# sanguish_2.net
KiCad netlist of a schematic drawn in EAGLE
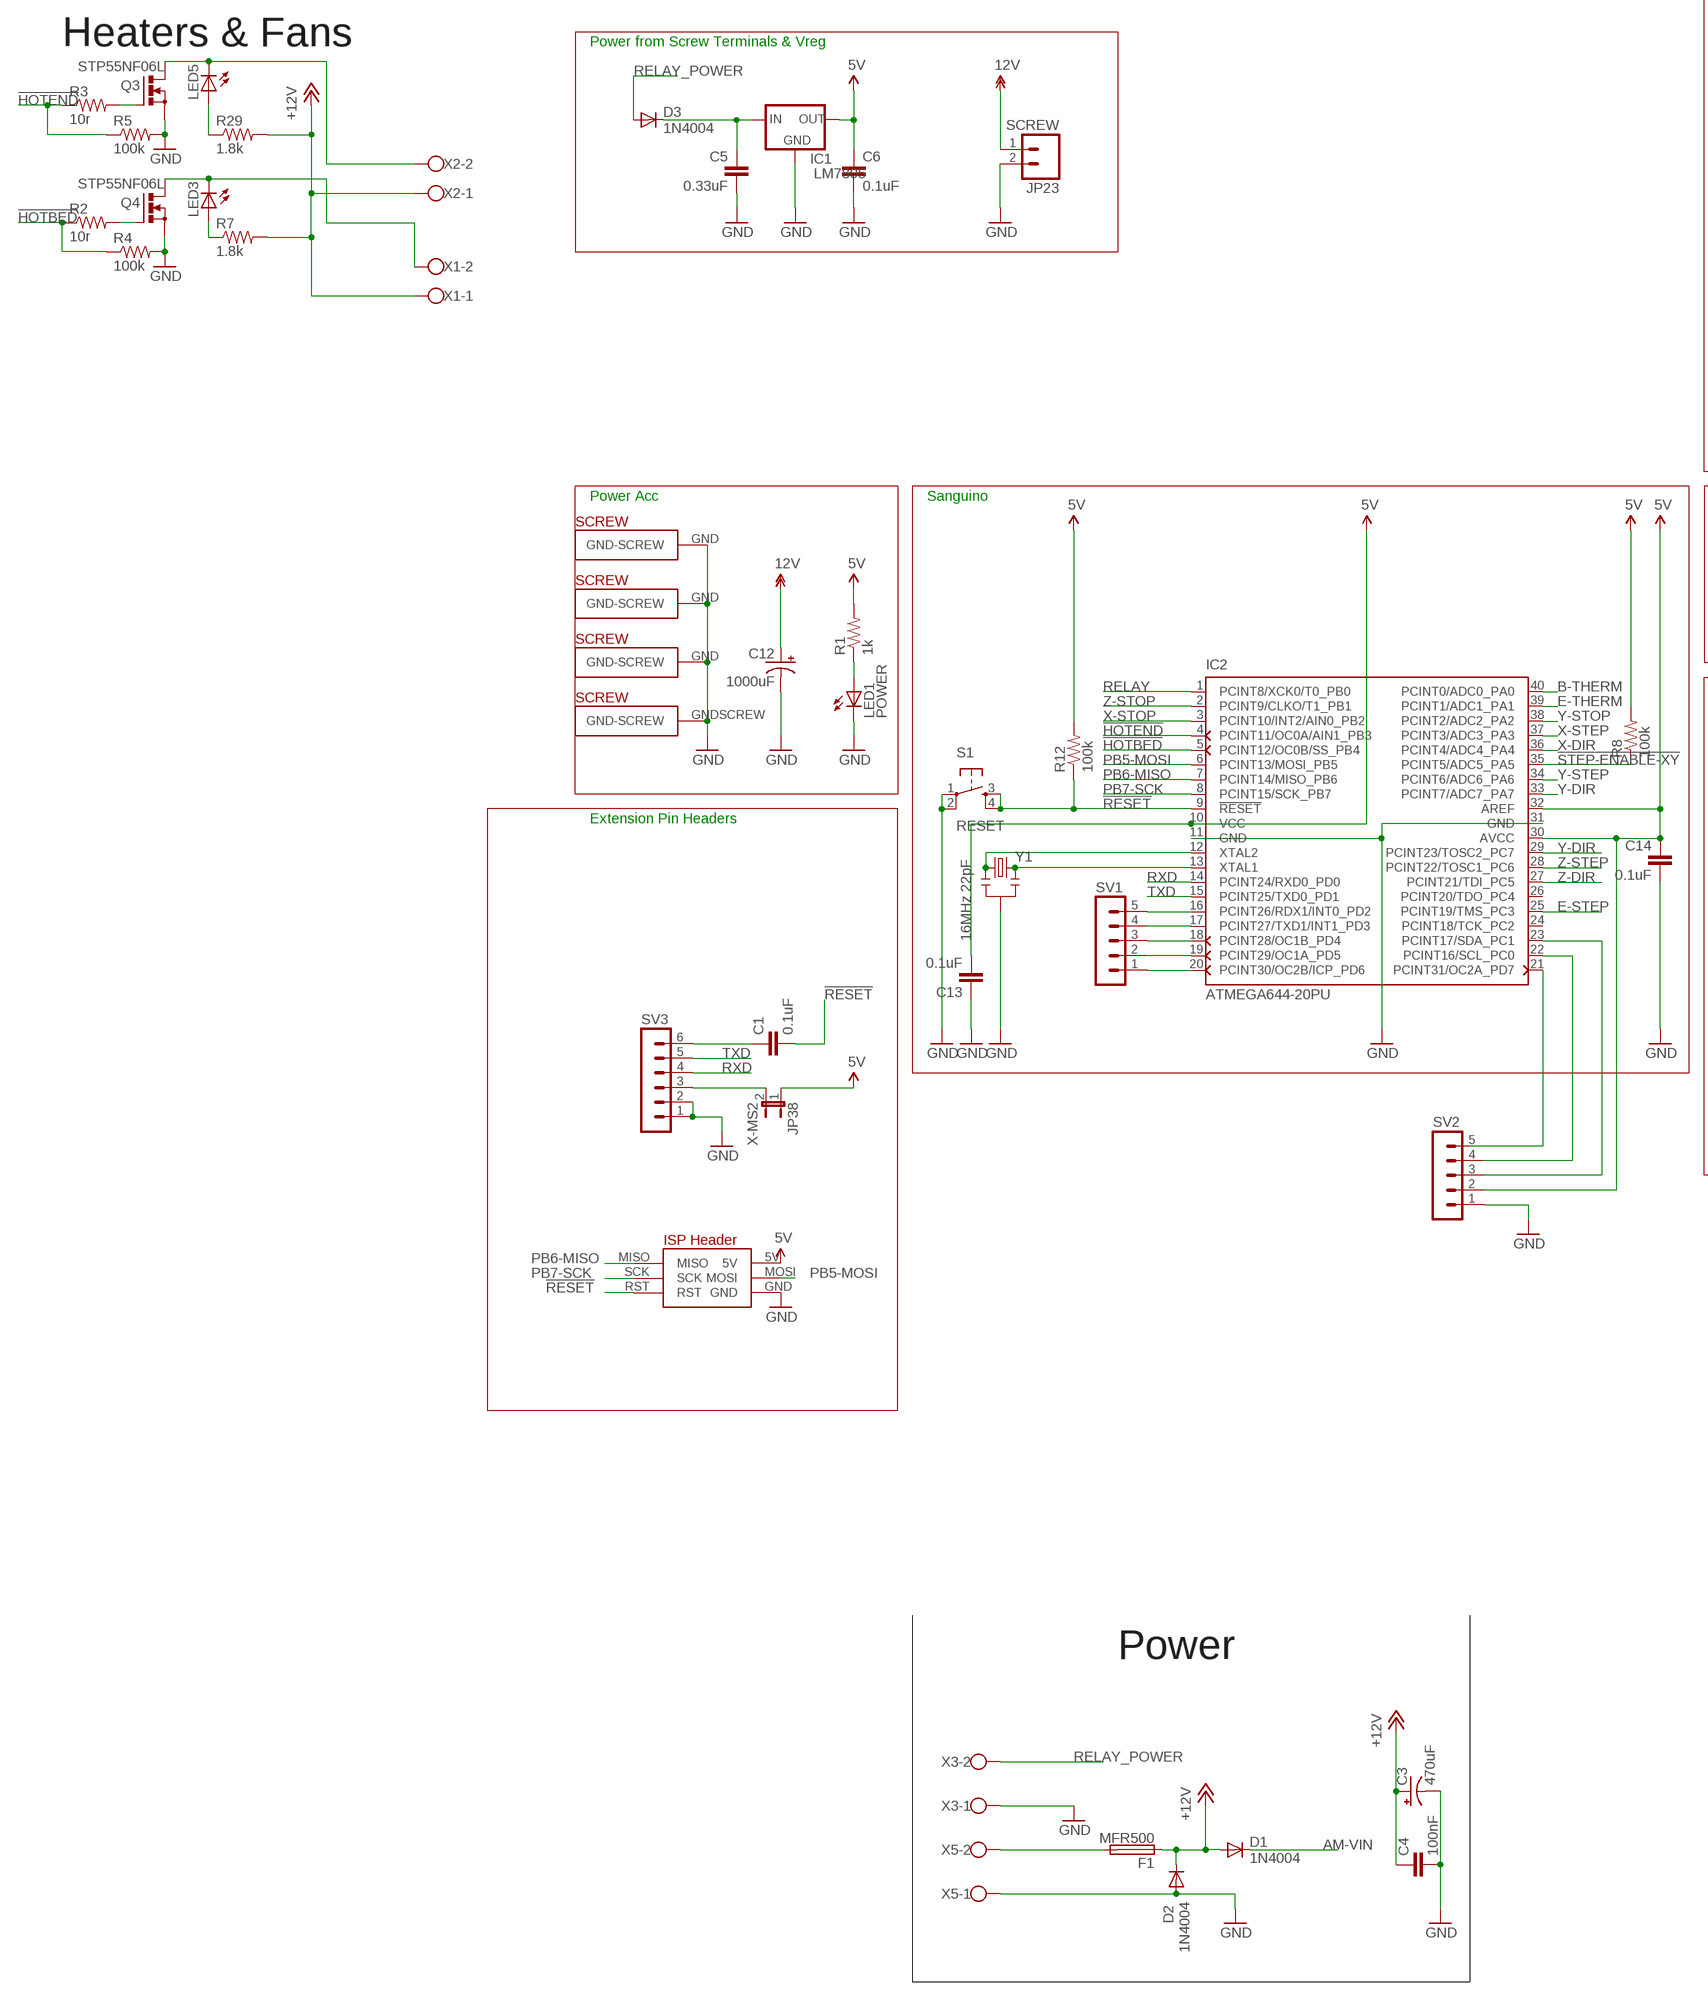
[diagram p0: schematic, sheet 1, part 1 of 2]
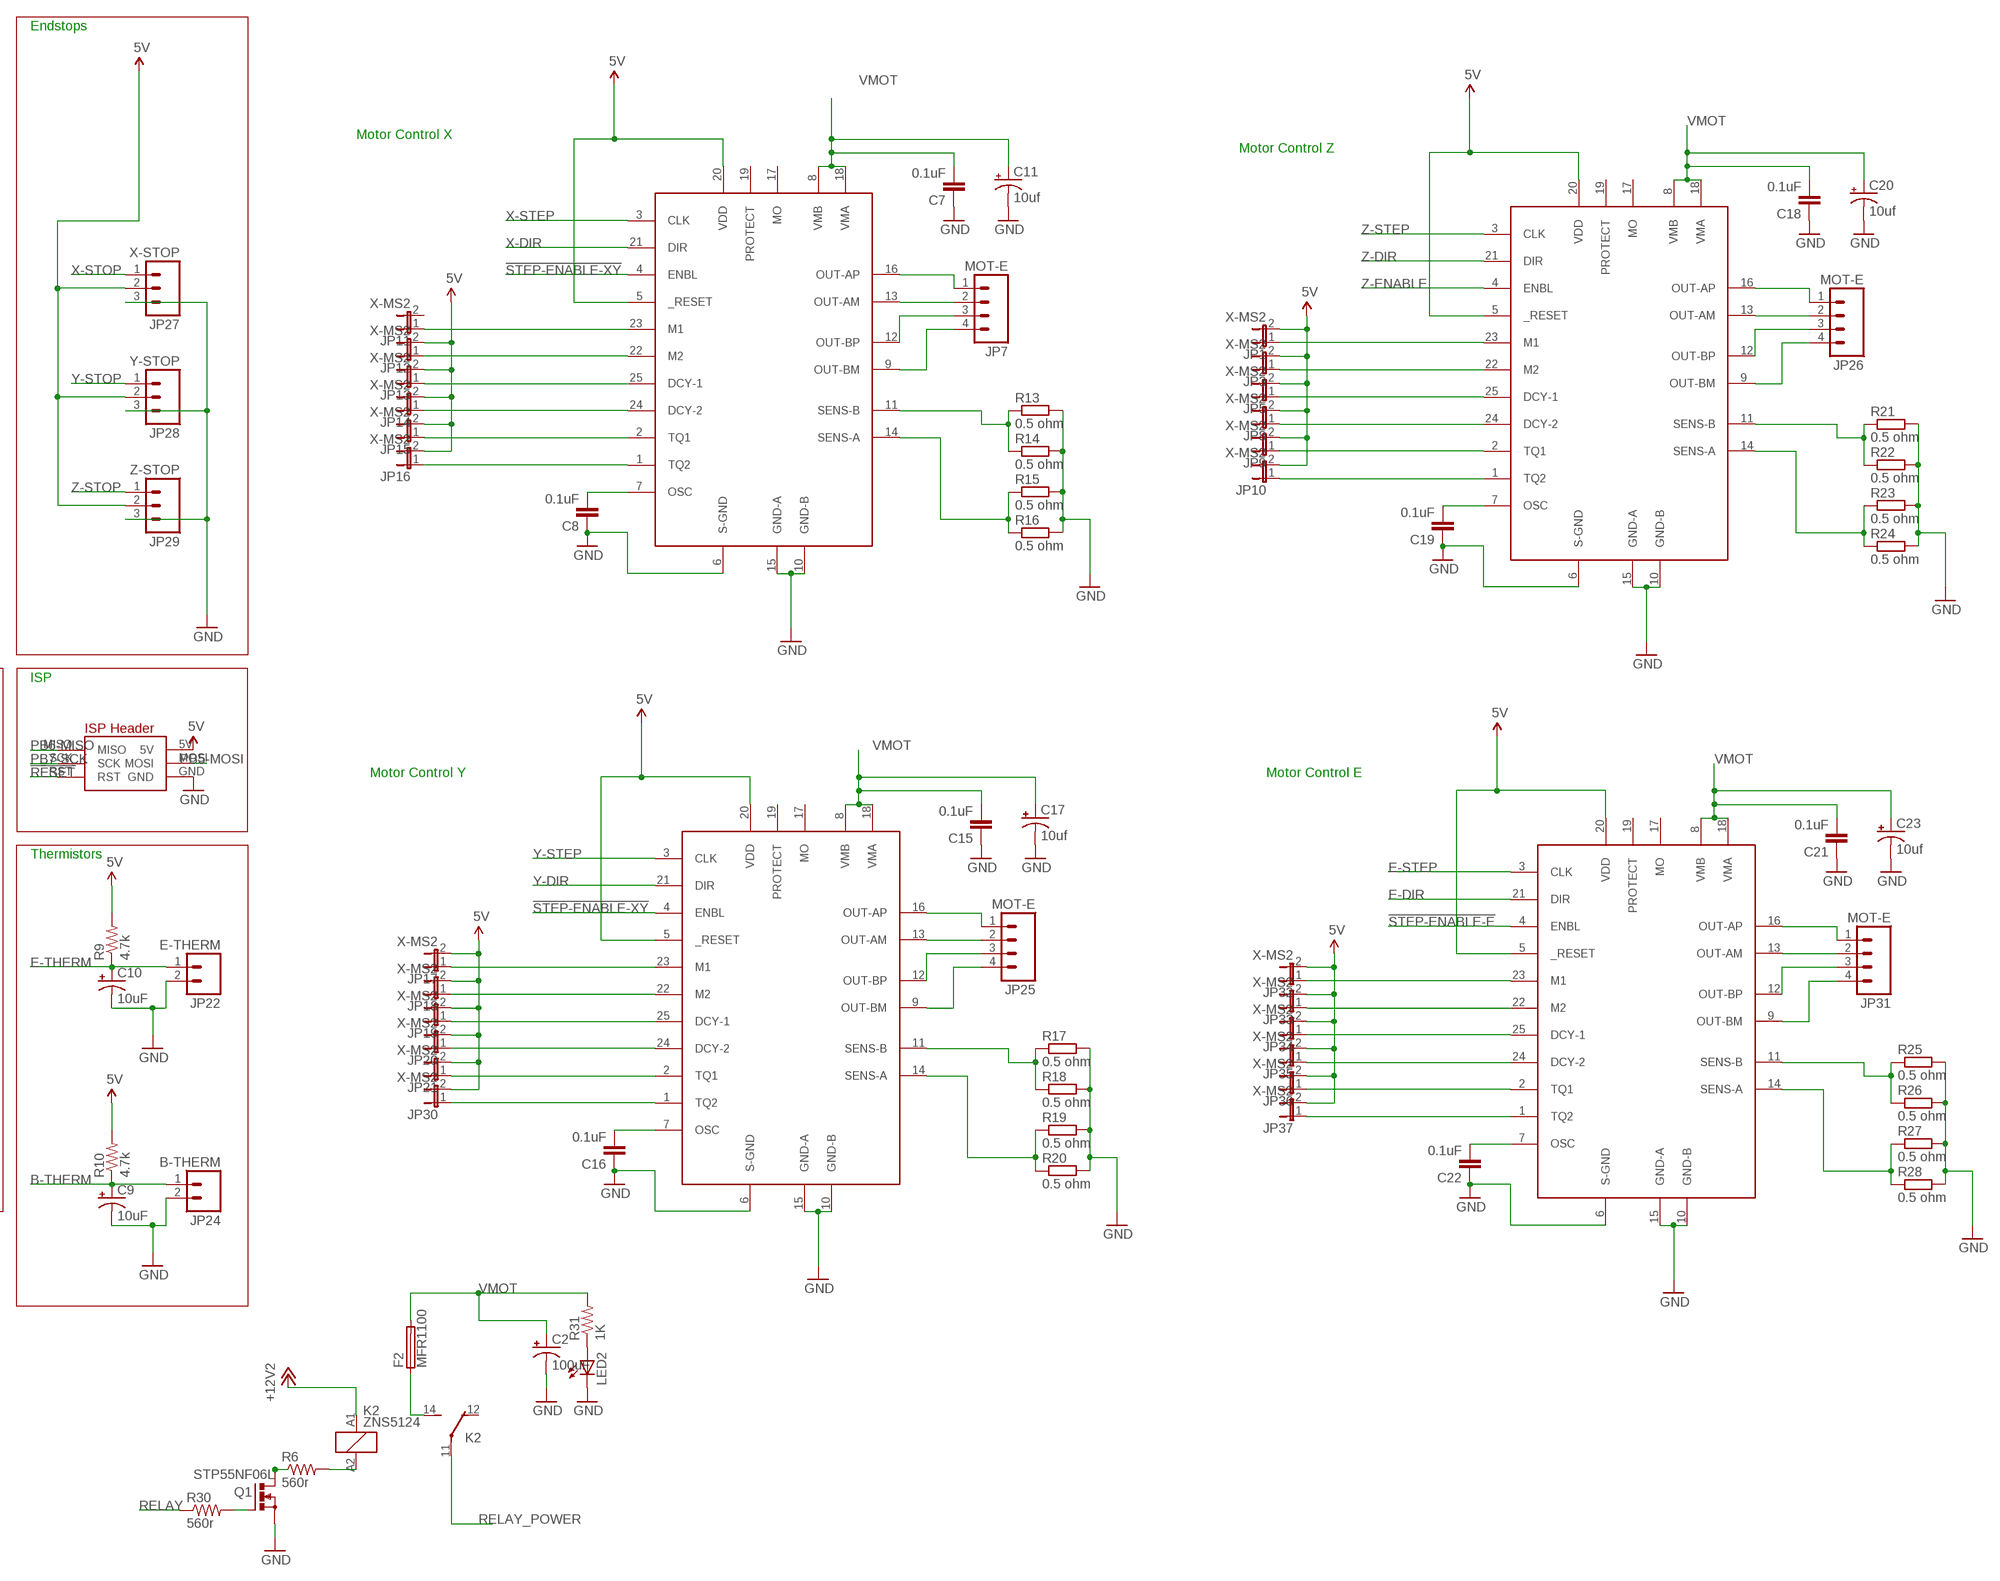
[diagram p1: schematic, sheet 1, part 2 of 2]

(export (version "E")
  (design (tool "Eeschema 10.0.6"))
  (components
    (comp (ref "C1")
      (value "0.1uF")
      (footprint "eagle-import:CAP-PTH-SMALL2")
      (libsource (lib "eagle-import") (part "CAPPTH2"))
    )
    (comp (ref "C2")
      (value "100uF")
      (footprint "eagle-import:CPOL-RADIAL-10UF-25V")
      (libsource (lib "eagle-import") (part "CAP_POLPTH2"))
    )
    (comp (ref "C3")
      (value "470uF")
      (footprint "eagle-import:E3,5-8")
      (libsource (lib "eagle-import") (part "CPOL-USE3.5-8"))
    )
    (comp (ref "C4")
      (value "100nF")
      (footprint "eagle-import:C2.5-3")
      (libsource (lib "eagle-import") (part "C2,5-3"))
    )
    (comp (ref "C5")
      (value "0.33uF")
      (footprint "eagle-import:CAP-PTH-SMALL2")
      (libsource (lib "eagle-import") (part "CAPPTH2"))
    )
    (comp (ref "C6")
      (value "0.1uF")
      (footprint "eagle-import:CAP-PTH-SMALL2")
      (libsource (lib "eagle-import") (part "CAPPTH2"))
    )
    (comp (ref "C7")
      (value "0.1uF")
      (footprint "eagle-import:CAP-PTH-SMALL2")
      (libsource (lib "eagle-import") (part "CAPPTH2"))
    )
    (comp (ref "C8")
      (value "0.1uF")
      (footprint "eagle-import:CAP-PTH-SMALL2")
      (libsource (lib "eagle-import") (part "CAPPTH2"))
    )
    (comp (ref "C9")
      (value "10uF")
      (footprint "eagle-import:CPOL-RADIAL-10UF-25V")
      (libsource (lib "eagle-import") (part "CAP_POLPTH2"))
    )
    (comp (ref "C10")
      (value "10uF")
      (footprint "eagle-import:CPOL-RADIAL-10UF-25V")
      (libsource (lib "eagle-import") (part "CAP_POLPTH2"))
    )
    (comp (ref "C11")
      (value "10uf")
      (footprint "eagle-import:CPOL-RADIAL-100UF-25V")
      (libsource (lib "eagle-import") (part "CAP_POLPTH1"))
    )
    (comp (ref "C12")
      (value "1000uF")
      (footprint "eagle-import:CPOL-RADIAL-1000UF-25V")
      (libsource (lib "eagle-import") (part "CAP_POLPTH4"))
    )
    (comp (ref "C13")
      (value "0.1uF")
      (footprint "eagle-import:CAP-PTH-SMALL2")
      (libsource (lib "eagle-import") (part "CAPPTH2"))
    )
    (comp (ref "C14")
      (value "0.1uF")
      (footprint "eagle-import:CAP-PTH-SMALL2")
      (libsource (lib "eagle-import") (part "CAPPTH2"))
    )
    (comp (ref "C15")
      (value "0.1uF")
      (footprint "eagle-import:CAP-PTH-SMALL2")
      (libsource (lib "eagle-import") (part "CAPPTH2"))
    )
    (comp (ref "C16")
      (value "0.1uF")
      (footprint "eagle-import:CAP-PTH-SMALL2")
      (libsource (lib "eagle-import") (part "CAPPTH2"))
    )
    (comp (ref "C17")
      (value "10uf")
      (footprint "eagle-import:CPOL-RADIAL-100UF-25V")
      (libsource (lib "eagle-import") (part "CAP_POLPTH1"))
    )
    (comp (ref "C18")
      (value "0.1uF")
      (footprint "eagle-import:CAP-PTH-SMALL2")
      (libsource (lib "eagle-import") (part "CAPPTH2"))
    )
    (comp (ref "C19")
      (value "0.1uF")
      (footprint "eagle-import:CAP-PTH-SMALL2")
      (libsource (lib "eagle-import") (part "CAPPTH2"))
    )
    (comp (ref "C20")
      (value "10uf")
      (footprint "eagle-import:CPOL-RADIAL-100UF-25V")
      (libsource (lib "eagle-import") (part "CAP_POLPTH1"))
    )
    (comp (ref "C21")
      (value "0.1uF")
      (footprint "eagle-import:CAP-PTH-SMALL2")
      (libsource (lib "eagle-import") (part "CAPPTH2"))
    )
    (comp (ref "C22")
      (value "0.1uF")
      (footprint "eagle-import:CAP-PTH-SMALL2")
      (libsource (lib "eagle-import") (part "CAPPTH2"))
    )
    (comp (ref "C23")
      (value "10uf")
      (footprint "eagle-import:CPOL-RADIAL-100UF-25V")
      (libsource (lib "eagle-import") (part "CAP_POLPTH1"))
    )
    (comp (ref "D1")
      (value "1N4004")
      (footprint "eagle-import:DO41-10")
      (libsource (lib "eagle-import") (part "1N4004"))
    )
    (comp (ref "D2")
      (value "1N4004")
      (footprint "eagle-import:DO41-10")
      (libsource (lib "eagle-import") (part "1N4004"))
    )
    (comp (ref "D3")
      (value "1N4004")
      (footprint "eagle-import:DO41-10")
      (libsource (lib "eagle-import") (part "1N4004"))
    )
    (comp (ref "F1")
      (value "MFR500")
      (footprint "eagle-import:MFR500")
      (libsource (lib "eagle-import") (part "PTCFUSE"))
    )
    (comp (ref "F2")
      (value "MFR1100")
      (footprint "eagle-import:MFR1100")
      (libsource (lib "eagle-import") (part "PTCFUSEMFR1100"))
    )
    (comp (ref "IC1")
      (value "LM7805")
      (footprint "eagle-import:78XXL-CUSTOM")
      (libsource (lib "eagle-import") (part "V_REG_78XX"))
    )
    (comp (ref "IC2")
      (value "ATMEGA644-20PU")
      (footprint "eagle-import:DIL40")
      (libsource (lib "eagle-import") (part "ATMEGA644-PU20"))
    )
    (comp (ref "JP1")
      (value "X-MS2")
      (footprint "eagle-import:1X02")
      (libsource (lib "eagle-import") (part "JUMPER-2PTH"))
    )
    (comp (ref "JP3")
      (value "X-MS2")
      (footprint "eagle-import:1X02")
      (libsource (lib "eagle-import") (part "JUMPER-2PTH"))
    )
    (comp (ref "JP5")
      (value "X-MS2")
      (footprint "eagle-import:1X02")
      (libsource (lib "eagle-import") (part "JUMPER-2PTH"))
    )
    (comp (ref "JP7")
      (value "MOT-E")
      (footprint "eagle-import:MOLEX-1X4")
      (libsource (lib "eagle-import") (part "M04POLAR"))
    )
    (comp (ref "JP8")
      (value "X-MS2")
      (footprint "eagle-import:1X02")
      (libsource (lib "eagle-import") (part "JUMPER-2PTH"))
    )
    (comp (ref "JP9")
      (value "X-MS2")
      (footprint "eagle-import:1X02")
      (libsource (lib "eagle-import") (part "JUMPER-2PTH"))
    )
    (comp (ref "JP10")
      (value "X-MS2")
      (footprint "eagle-import:1X02")
      (libsource (lib "eagle-import") (part "JUMPER-2PTH"))
    )
    (comp (ref "JP11")
      (value "X-MS2")
      (footprint "eagle-import:1X02")
      (libsource (lib "eagle-import") (part "JUMPER-2PTH"))
    )
    (comp (ref "JP12")
      (value "X-MS2")
      (footprint "eagle-import:1X02")
      (libsource (lib "eagle-import") (part "JUMPER-2PTH"))
    )
    (comp (ref "JP13")
      (value "X-MS2")
      (footprint "eagle-import:1X02")
      (libsource (lib "eagle-import") (part "JUMPER-2PTH"))
    )
    (comp (ref "JP14")
      (value "X-MS2")
      (footprint "eagle-import:1X02")
      (libsource (lib "eagle-import") (part "JUMPER-2PTH"))
    )
    (comp (ref "JP15")
      (value "X-MS2")
      (footprint "eagle-import:1X02")
      (libsource (lib "eagle-import") (part "JUMPER-2PTH"))
    )
    (comp (ref "JP16")
      (value "X-MS2")
      (footprint "eagle-import:1X02")
      (libsource (lib "eagle-import") (part "JUMPER-2PTH"))
    )
    (comp (ref "JP17")
      (value "X-MS2")
      (footprint "eagle-import:1X02")
      (libsource (lib "eagle-import") (part "JUMPER-2PTH"))
    )
    (comp (ref "JP18")
      (value "X-MS2")
      (footprint "eagle-import:1X02")
      (libsource (lib "eagle-import") (part "JUMPER-2PTH"))
    )
    (comp (ref "JP19")
      (value "X-MS2")
      (footprint "eagle-import:1X02")
      (libsource (lib "eagle-import") (part "JUMPER-2PTH"))
    )
    (comp (ref "JP20")
      (value "X-MS2")
      (footprint "eagle-import:1X02")
      (libsource (lib "eagle-import") (part "JUMPER-2PTH"))
    )
    (comp (ref "JP21")
      (value "X-MS2")
      (footprint "eagle-import:1X02")
      (libsource (lib "eagle-import") (part "JUMPER-2PTH"))
    )
    (comp (ref "JP22")
      (value "E-THERM")
      (footprint "eagle-import:1X02")
      (libsource (lib "eagle-import") (part "M02PTH"))
    )
    (comp (ref "JP23")
      (value "SCREW")
      (footprint "eagle-import:SCREWTERMINAL-5MM-2")
      (libsource (lib "eagle-import") (part "M025MM"))
    )
    (comp (ref "JP24")
      (value "B-THERM")
      (footprint "eagle-import:1X02")
      (libsource (lib "eagle-import") (part "M02PTH"))
    )
    (comp (ref "JP25")
      (value "MOT-E")
      (footprint "eagle-import:MOLEX-1X4")
      (libsource (lib "eagle-import") (part "M04POLAR"))
    )
    (comp (ref "JP26")
      (value "MOT-E")
      (footprint "eagle-import:MOLEX-1X4")
      (libsource (lib "eagle-import") (part "M04POLAR"))
    )
    (comp (ref "JP27")
      (value "X-STOP")
      (footprint "eagle-import:MOLEX-1X3")
      (libsource (lib "eagle-import") (part "M03POLAR"))
    )
    (comp (ref "JP28")
      (value "Y-STOP")
      (footprint "eagle-import:MOLEX-1X3")
      (libsource (lib "eagle-import") (part "M03POLAR"))
    )
    (comp (ref "JP29")
      (value "Z-STOP")
      (footprint "eagle-import:MOLEX-1X3")
      (libsource (lib "eagle-import") (part "M03POLAR"))
    )
    (comp (ref "JP30")
      (value "X-MS2")
      (footprint "eagle-import:1X02")
      (libsource (lib "eagle-import") (part "JUMPER-2PTH"))
    )
    (comp (ref "JP31")
      (value "MOT-E")
      (footprint "eagle-import:MOLEX-1X4")
      (libsource (lib "eagle-import") (part "M04POLAR"))
    )
    (comp (ref "JP32")
      (value "X-MS2")
      (footprint "eagle-import:1X02")
      (libsource (lib "eagle-import") (part "JUMPER-2PTH"))
    )
    (comp (ref "JP33")
      (value "X-MS2")
      (footprint "eagle-import:1X02")
      (libsource (lib "eagle-import") (part "JUMPER-2PTH"))
    )
    (comp (ref "JP34")
      (value "X-MS2")
      (footprint "eagle-import:1X02")
      (libsource (lib "eagle-import") (part "JUMPER-2PTH"))
    )
    (comp (ref "JP35")
      (value "X-MS2")
      (footprint "eagle-import:1X02")
      (libsource (lib "eagle-import") (part "JUMPER-2PTH"))
    )
    (comp (ref "JP36")
      (value "X-MS2")
      (footprint "eagle-import:1X02")
      (libsource (lib "eagle-import") (part "JUMPER-2PTH"))
    )
    (comp (ref "JP37")
      (value "X-MS2")
      (footprint "eagle-import:1X02")
      (libsource (lib "eagle-import") (part "JUMPER-2PTH"))
    )
    (comp (ref "JP38")
      (value "X-MS2")
      (footprint "eagle-import:1X02")
      (libsource (lib "eagle-import") (part "JUMPER-2PTH"))
    )
    (comp (ref "K2")
      (value "ZNS5124")
      (footprint "eagle-import:ZN5")
      (libsource (lib "eagle-import") (part "ZNS5124"))
    )
    (comp (ref "LED1")
      (value "POWER")
      (footprint "eagle-import:LED3MM")
      (libsource (lib "eagle-import") (part "LED3MM"))
    )
    (comp (ref "LED2")
      (value "LED3MM")
      (footprint "eagle-import:LED3MM")
      (libsource (lib "eagle-import") (part "led_LED3MM"))
    )
    (comp (ref "LED3")
      (value "LED3MM")
      (footprint "eagle-import:LED3MM")
      (libsource (lib "eagle-import") (part "led_LED3MM"))
    )
    (comp (ref "LED5")
      (value "LED3MM")
      (footprint "eagle-import:LED3MM")
      (libsource (lib "eagle-import") (part "led_LED3MM"))
    )
    (comp (ref "Q1")
      (value "STP55NF06L")
      (footprint "eagle-import:TO220BV")
      (libsource (lib "eagle-import") (part "IRF512"))
    )
    (comp (ref "Q3")
      (value "STP55NF06L")
      (footprint "eagle-import:TO220BV")
      (libsource (lib "eagle-import") (part "IRF512"))
    )
    (comp (ref "Q4")
      (value "STP55NF06L")
      (footprint "eagle-import:TO220BV")
      (libsource (lib "eagle-import") (part "IRF512"))
    )
    (comp (ref "R1")
      (value "1k")
      (footprint "eagle-import:AXIAL-0.3")
      (libsource (lib "eagle-import") (part "RESISTORPTH1"))
    )
    (comp (ref "R2")
      (value "10r")
      (footprint "eagle-import:0207_2V")
      (libsource (lib "eagle-import") (part "resistor_R-US_0207/2V"))
    )
    (comp (ref "R3")
      (value "10r")
      (footprint "eagle-import:0207_2V")
      (libsource (lib "eagle-import") (part "resistor_R-US_0207/2V"))
    )
    (comp (ref "R4")
      (value "100k")
      (footprint "eagle-import:0207_2V")
      (libsource (lib "eagle-import") (part "resistor_R-US_0207/2V"))
    )
    (comp (ref "R5")
      (value "100k")
      (footprint "eagle-import:0207_2V")
      (libsource (lib "eagle-import") (part "resistor_R-US_0207/2V"))
    )
    (comp (ref "R6")
      (value "560r")
      (footprint "eagle-import:0207_2V")
      (libsource (lib "eagle-import") (part "resistor_R-US_0207/2V"))
    )
    (comp (ref "R7")
      (value "1.8k")
      (footprint "eagle-import:0207_2V")
      (libsource (lib "eagle-import") (part "resistor_R-US_0207/2V"))
    )
    (comp (ref "R8")
      (value "100k")
      (footprint "eagle-import:AXIAL-0.3")
      (libsource (lib "eagle-import") (part "RESISTORPTH1"))
    )
    (comp (ref "R9")
      (value "4.7k")
      (footprint "eagle-import:AXIAL-0.3")
      (libsource (lib "eagle-import") (part "RESISTORPTH1"))
    )
    (comp (ref "R10")
      (value "4.7k")
      (footprint "eagle-import:AXIAL-0.3")
      (libsource (lib "eagle-import") (part "RESISTORPTH1"))
    )
    (comp (ref "R12")
      (value "100k")
      (footprint "eagle-import:AXIAL-0.3")
      (libsource (lib "eagle-import") (part "RESISTORPTH1"))
    )
    (comp (ref "R13")
      (value "0.5 ohm")
      (footprint "eagle-import:0207_10")
      (libsource (lib "eagle-import") (part "R-EU_0207/10"))
    )
    (comp (ref "R14")
      (value "0.5 ohm")
      (footprint "eagle-import:0207_10")
      (libsource (lib "eagle-import") (part "R-EU_0207/10"))
    )
    (comp (ref "R15")
      (value "0.5 ohm")
      (footprint "eagle-import:0207_10")
      (libsource (lib "eagle-import") (part "R-EU_0207/10"))
    )
    (comp (ref "R16")
      (value "0.5 ohm")
      (footprint "eagle-import:0207_10")
      (libsource (lib "eagle-import") (part "R-EU_0207/10"))
    )
    (comp (ref "R17")
      (value "0.5 ohm")
      (footprint "eagle-import:0207_10")
      (libsource (lib "eagle-import") (part "R-EU_0207/10"))
    )
    (comp (ref "R18")
      (value "0.5 ohm")
      (footprint "eagle-import:0207_10")
      (libsource (lib "eagle-import") (part "R-EU_0207/10"))
    )
    (comp (ref "R19")
      (value "0.5 ohm")
      (footprint "eagle-import:0207_10")
      (libsource (lib "eagle-import") (part "R-EU_0207/10"))
    )
    (comp (ref "R20")
      (value "0.5 ohm")
      (footprint "eagle-import:0207_10")
      (libsource (lib "eagle-import") (part "R-EU_0207/10"))
    )
    (comp (ref "R21")
      (value "0.5 ohm")
      (footprint "eagle-import:0207_10")
      (libsource (lib "eagle-import") (part "R-EU_0207/10"))
    )
    (comp (ref "R22")
      (value "0.5 ohm")
      (footprint "eagle-import:0207_10")
      (libsource (lib "eagle-import") (part "R-EU_0207/10"))
    )
    (comp (ref "R23")
      (value "0.5 ohm")
      (footprint "eagle-import:0207_10")
      (libsource (lib "eagle-import") (part "R-EU_0207/10"))
    )
    (comp (ref "R24")
      (value "0.5 ohm")
      (footprint "eagle-import:0207_10")
      (libsource (lib "eagle-import") (part "R-EU_0207/10"))
    )
    (comp (ref "R25")
      (value "0.5 ohm")
      (footprint "eagle-import:0207_10")
      (libsource (lib "eagle-import") (part "R-EU_0207/10"))
    )
    (comp (ref "R26")
      (value "0.5 ohm")
      (footprint "eagle-import:0207_10")
      (libsource (lib "eagle-import") (part "R-EU_0207/10"))
    )
    (comp (ref "R27")
      (value "0.5 ohm")
      (footprint "eagle-import:0207_10")
      (libsource (lib "eagle-import") (part "R-EU_0207/10"))
    )
    (comp (ref "R28")
      (value "0.5 ohm")
      (footprint "eagle-import:0207_10")
      (libsource (lib "eagle-import") (part "R-EU_0207/10"))
    )
    (comp (ref "R29")
      (value "1.8k")
      (footprint "eagle-import:0207_2V")
      (libsource (lib "eagle-import") (part "resistor_R-US_0207/2V"))
    )
    (comp (ref "R30")
      (value "560r")
      (footprint "eagle-import:0207_2V")
      (libsource (lib "eagle-import") (part "resistor_R-US_0207/2V"))
    )
    (comp (ref "R31")
      (value "1K")
      (footprint "eagle-import:0207_7")
      (libsource (lib "eagle-import") (part "R-US_0207/7"))
    )
    (comp (ref "S1")
      (value "RESET")
      (footprint "eagle-import:TACTILE-PTH")
      (libsource (lib "eagle-import") (part "TAC_SWITCHPTH"))
    )
    (comp (ref "SV1")
      (value "MA05-1")
      (footprint "eagle-import:MA05-1")
      (libsource (lib "eagle-import") (part "MA05-1"))
    )
    (comp (ref "SV2")
      (value "MA05-1")
      (footprint "eagle-import:MA05-1")
      (fields (field (name "OC_FARNELL") "unknown") (field (name "OC_NEWARK") "unknown"))
      (libsource (lib "eagle-import") (part "MA05-1"))
    )
    (comp (ref "SV3")
      (value "MA06-1")
      (footprint "eagle-import:MA06-1")
      (libsource (lib "eagle-import") (part "MA06-1"))
    )
    (comp (ref "U$10")
      (value "IO_HEADERS_SCREW")
      (footprint "eagle-import:IO_HEADER-PLATEDSCREW")
      (libsource (lib "eagle-import") (part "IO_HEADERS_SCREW"))
    )
    (comp (ref "U$17")
      (value "PLATED-SCREW")
      (footprint "eagle-import:PLATEDSCREW")
      (libsource (lib "eagle-import") (part "PLATED-SCREW"))
    )
    (comp (ref "U$21")
      (value "TB6560")
      (footprint "eagle-import:ZIP25")
      (libsource (lib "eagle-import") (part "TB6560"))
    )
    (comp (ref "U$24")
      (value "IO_HEADERS_SCREW")
      (footprint "eagle-import:IO_HEADER-PLATEDSCREW")
      (libsource (lib "eagle-import") (part "IO_HEADERS_SCREW"))
    )
    (comp (ref "U$37")
      (value "PLATED-SCREW")
      (footprint "eagle-import:PLATEDSCREW")
      (libsource (lib "eagle-import") (part "PLATED-SCREW"))
    )
    (comp (ref "U$38")
      (value "PLATED-SCREW")
      (footprint "eagle-import:PLATEDSCREW")
      (libsource (lib "eagle-import") (part "PLATED-SCREW"))
    )
    (comp (ref "U$41")
      (value "TB6560")
      (footprint "eagle-import:ZIP25")
      (libsource (lib "eagle-import") (part "TB6560"))
    )
    (comp (ref "U$43")
      (value "TB6560")
      (footprint "eagle-import:ZIP25")
      (libsource (lib "eagle-import") (part "TB6560"))
    )
    (comp (ref "U$46")
      (value "TB6560")
      (footprint "eagle-import:ZIP25")
      (libsource (lib "eagle-import") (part "TB6560"))
    )
    (comp (ref "X1")
      (value "W237-102")
      (footprint "eagle-import:W237-102")
      (fields
        (field (name "MPN") "237-102")
        (field (name "MPN_1") "237-102")
        (field (name "OC_FARNELL") "unknown")
        (field (name "OC_NEWARK") "70K9898")
      )
      (libsource (lib "eagle-import") (part "W237-102"))
    )
    (comp (ref "X2")
      (value "W237-102")
      (footprint "eagle-import:W237-102")
      (fields (field (name "MPN") "237-102"))
      (libsource (lib "eagle-import") (part "W237-102"))
    )
    (comp (ref "X3")
      (value "W237-102")
      (footprint "eagle-import:W237-102")
      (fields
        (field (name "MPN") "237-102")
        (field (name "MPN_1") "237-102")
        (field (name "OC_FARNELL") "unknown")
        (field (name "OC_NEWARK") "70K9898")
      )
      (libsource (lib "eagle-import") (part "W237-102"))
    )
    (comp (ref "X5")
      (value "W237-102")
      (footprint "eagle-import:W237-102")
      (fields
        (field (name "MPN") "237-102")
        (field (name "MPN_1") "237-102")
        (field (name "OC_FARNELL") "unknown")
        (field (name "OC_NEWARK") "70K9898")
      )
      (libsource (lib "eagle-import") (part "W237-102"))
    )
    (comp (ref "Y1")
      (value "16MHz 22pF")
      (footprint "eagle-import:RESONATOR-PTH")
      (libsource (lib "eagle-import") (part "RESONATORPTH"))
    )
  )
  (nets
    (net (code "1") (name "+12V") (class "Default")
      (node (ref "C3") (pin "+") (pinfunction "+_+") (pintype "passive"))
      (node (ref "C4") (pin "1") (pinfunction "1_1") (pintype "passive"))
      (node (ref "D1") (pin "A") (pinfunction "A_A") (pintype "passive"))
      (node (ref "D2") (pin "C") (pinfunction "C_C") (pintype "passive"))
      (node (ref "F1") (pin "1") (pinfunction "1_1") (pintype "passive"))
      (node (ref "K2") (pin "A1") (pinfunction "1_A1") (pintype "passive"))
      (node (ref "R29") (pin "2") (pinfunction "2_2") (pintype "passive"))
      (node (ref "R7") (pin "2") (pinfunction "2_2") (pintype "passive"))
      (node (ref "X1") (pin "1") (pinfunction "KL_1") (pintype "passive"))
      (node (ref "X2") (pin "1") (pinfunction "KL_1") (pintype "passive"))
    )
    (net (code "2") (name "/AM-VIN") (class "Default")
      (node (ref "D1") (pin "C") (pinfunction "C_C") (pintype "passive"))
    )
    (net (code "3") (name "/B-THERM") (class "Default")
      (node (ref "C9") (pin "1") (pinfunction "+_1") (pintype "passive"))
      (node (ref "IC2") (pin "40") (pinfunction "PCINT0/ADC0_PA0_40") (pintype "bidirectional"))
      (node (ref "JP24") (pin "1") (pinfunction "1_1") (pintype "passive"))
      (node (ref "R10") (pin "P$1") (pinfunction "1_P$1") (pintype "passive"))
    )
    (net (code "4") (name "/E-DIR") (class "Default")
      (node (ref "U$46") (pin "21") (pinfunction "DIR_21") (pintype "bidirectional"))
    )
    (net (code "5") (name "/E-STEP") (class "Default")
      (node (ref "IC2") (pin "25") (pinfunction "PCINT19/TMS_PC3_25") (pintype "bidirectional"))
      (node (ref "U$46") (pin "3") (pinfunction "CLK_3") (pintype "bidirectional"))
    )
    (net (code "6") (name "/E-THERM") (class "Default")
      (node (ref "C10") (pin "1") (pinfunction "+_1") (pintype "passive"))
      (node (ref "IC2") (pin "39") (pinfunction "PCINT1/ADC1_PA1_39") (pintype "bidirectional"))
      (node (ref "JP22") (pin "1") (pinfunction "1_1") (pintype "passive"))
      (node (ref "R9") (pin "P$1") (pinfunction "1_P$1") (pintype "passive"))
    )
    (net (code "7") (name "/PB5-MOSI") (class "Default")
      (node (ref "IC2") (pin "6") (pinfunction "PCINT13/MOSI_PB5_6") (pintype "bidirectional"))
      (node (ref "U$10") (pin "MOSI") (pinfunction "MOSI_MOSI") (pintype "bidirectional"))
      (node (ref "U$24") (pin "MOSI") (pinfunction "MOSI_MOSI") (pintype "bidirectional"))
    )
    (net (code "8") (name "/PB6-MISO") (class "Default")
      (node (ref "IC2") (pin "7") (pinfunction "PCINT14/MISO_PB6_7") (pintype "bidirectional"))
      (node (ref "U$10") (pin "MISO") (pinfunction "MISO_MISO") (pintype "bidirectional"))
      (node (ref "U$24") (pin "MISO") (pinfunction "MISO_MISO") (pintype "bidirectional"))
    )
    (net (code "9") (name "/PB7-SCK") (class "Default")
      (node (ref "IC2") (pin "8") (pinfunction "PCINT15/SCK_PB7_8") (pintype "bidirectional"))
      (node (ref "U$10") (pin "SCK") (pinfunction "SCK_SCK") (pintype "bidirectional"))
      (node (ref "U$24") (pin "SCK") (pinfunction "SCK_SCK") (pintype "bidirectional"))
    )
    (net (code "10") (name "/RELAY") (class "Default")
      (node (ref "IC2") (pin "1") (pinfunction "PCINT8/XCK0/T0_PB0_1") (pintype "bidirectional"))
      (node (ref "R30") (pin "1") (pinfunction "1_1") (pintype "passive"))
    )
    (net (code "11") (name "/RELAY_POWER") (class "Default")
      (node (ref "D3") (pin "A") (pinfunction "A_A") (pintype "passive"))
      (node (ref "K2") (pin "11") (pinfunction "P_11") (pintype "passive"))
      (node (ref "X3") (pin "2") (pinfunction "KL_2") (pintype "passive"))
    )
    (net (code "12") (name "/RXD") (class "Default")
      (node (ref "IC2") (pin "14") (pinfunction "PCINT24/RXD0_PD0_14") (pintype "bidirectional"))
      (node (ref "SV3") (pin "4") (pinfunction "4_4") (pintype "passive"))
    )
    (net (code "13") (name "/TXD") (class "Default")
      (node (ref "IC2") (pin "15") (pinfunction "PCINT25/TXD0_PD1_15") (pintype "bidirectional"))
      (node (ref "SV3") (pin "5") (pinfunction "5_5") (pintype "passive"))
    )
    (net (code "14") (name "/VMOT") (class "Default")
      (node (ref "C11") (pin "1") (pinfunction "+_1") (pintype "passive"))
      (node (ref "C15") (pin "2") (pinfunction "2_2") (pintype "passive"))
      (node (ref "C17") (pin "1") (pinfunction "+_1") (pintype "passive"))
      (node (ref "C18") (pin "2") (pinfunction "2_2") (pintype "passive"))
      (node (ref "C2") (pin "1") (pinfunction "+_1") (pintype "passive"))
      (node (ref "C20") (pin "1") (pinfunction "+_1") (pintype "passive"))
      (node (ref "C21") (pin "2") (pinfunction "2_2") (pintype "passive"))
      (node (ref "C23") (pin "1") (pinfunction "+_1") (pintype "passive"))
      (node (ref "C7") (pin "2") (pinfunction "2_2") (pintype "passive"))
      (node (ref "F2") (pin "2") (pinfunction "2_2") (pintype "passive"))
      (node (ref "R31") (pin "2") (pinfunction "2_2") (pintype "passive"))
      (node (ref "U$21") (pin "18") (pinfunction "VMA_18") (pintype "bidirectional"))
      (node (ref "U$21") (pin "8") (pinfunction "VMB_8") (pintype "bidirectional"))
      (node (ref "U$41") (pin "18") (pinfunction "VMA_18") (pintype "bidirectional"))
      (node (ref "U$41") (pin "8") (pinfunction "VMB_8") (pintype "bidirectional"))
      (node (ref "U$43") (pin "18") (pinfunction "VMA_18") (pintype "bidirectional"))
      (node (ref "U$43") (pin "8") (pinfunction "VMB_8") (pintype "bidirectional"))
      (node (ref "U$46") (pin "18") (pinfunction "VMA_18") (pintype "bidirectional"))
      (node (ref "U$46") (pin "8") (pinfunction "VMB_8") (pintype "bidirectional"))
    )
    (net (code "15") (name "/X-DIR") (class "Default")
      (node (ref "IC2") (pin "36") (pinfunction "PCINT4/ADC4_PA4_36") (pintype "bidirectional"))
      (node (ref "U$41") (pin "21") (pinfunction "DIR_21") (pintype "bidirectional"))
    )
    (net (code "16") (name "/X-STEP") (class "Default")
      (node (ref "IC2") (pin "37") (pinfunction "PCINT3/ADC3_PA3_37") (pintype "bidirectional"))
      (node (ref "U$41") (pin "3") (pinfunction "CLK_3") (pintype "bidirectional"))
    )
    (net (code "17") (name "/X-STOP") (class "Default")
      (node (ref "IC2") (pin "3") (pinfunction "PCINT10/INT2/AIN0_PB2_3") (pintype "bidirectional"))
      (node (ref "JP27") (pin "1") (pinfunction "1_1") (pintype "passive"))
    )
    (net (code "18") (name "/Y-DIR") (class "Default")
      (node (ref "IC2") (pin "29") (pinfunction "PCINT23/TOSC2_PC7_29") (pintype "bidirectional"))
      (node (ref "IC2") (pin "33") (pinfunction "PCINT7/ADC7_PA7_33") (pintype "bidirectional"))
      (node (ref "U$21") (pin "21") (pinfunction "DIR_21") (pintype "bidirectional"))
    )
    (net (code "19") (name "/Y-STEP") (class "Default")
      (node (ref "IC2") (pin "34") (pinfunction "PCINT6/ADC6_PA6_34") (pintype "bidirectional"))
      (node (ref "U$21") (pin "3") (pinfunction "CLK_3") (pintype "bidirectional"))
    )
    (net (code "20") (name "/Y-STOP") (class "Default")
      (node (ref "IC2") (pin "38") (pinfunction "PCINT2/ADC2_PA2_38") (pintype "bidirectional"))
      (node (ref "JP28") (pin "1") (pinfunction "1_1") (pintype "passive"))
    )
    (net (code "21") (name "/Z-DIR") (class "Default")
      (node (ref "IC2") (pin "27") (pinfunction "PCINT21/TDI_PC5_27") (pintype "bidirectional"))
      (node (ref "U$43") (pin "21") (pinfunction "DIR_21") (pintype "bidirectional"))
    )
    (net (code "22") (name "/Z-ENABLE") (class "Default")
      (node (ref "U$43") (pin "4") (pinfunction "ENBL_4") (pintype "bidirectional"))
    )
    (net (code "23") (name "/Z-STEP") (class "Default")
      (node (ref "IC2") (pin "28") (pinfunction "PCINT22/TOSC1_PC6_28") (pintype "bidirectional"))
      (node (ref "U$43") (pin "3") (pinfunction "CLK_3") (pintype "bidirectional"))
    )
    (net (code "24") (name "/Z-STOP") (class "Default")
      (node (ref "IC2") (pin "2") (pinfunction "PCINT9/CLKO/T1_PB1_2") (pintype "bidirectional"))
      (node (ref "JP29") (pin "1") (pinfunction "1_1") (pintype "passive"))
    )
    (net (code "25") (name "/~{HOTBED}") (class "Default")
      (node (ref "IC2") (pin "5") (pinfunction "PCINT12/OC0B/SS_PB4_5") (pintype "bidirectional"))
      (node (ref "R2") (pin "1") (pinfunction "1_1") (pintype "passive"))
      (node (ref "R4") (pin "1") (pinfunction "1_1") (pintype "passive"))
    )
    (net (code "26") (name "/~{HOTEND}") (class "Default")
      (node (ref "IC2") (pin "4") (pinfunction "PCINT11/OC0A/AIN1_PB3_4") (pintype "bidirectional"))
      (node (ref "R3") (pin "1") (pinfunction "1_1") (pintype "passive"))
      (node (ref "R5") (pin "1") (pinfunction "1_1") (pintype "passive"))
    )
    (net (code "27") (name "/~{RESET}") (class "Default")
      (node (ref "C1") (pin "2") (pinfunction "2_2") (pintype "passive"))
      (node (ref "IC2") (pin "9") (pinfunction "~{RESET}_9") (pintype "input"))
      (node (ref "R12") (pin "P$1") (pinfunction "1_P$1") (pintype "passive"))
      (node (ref "S1") (pin "3") (pinfunction "3_3") (pintype "passive"))
      (node (ref "S1") (pin "4") (pinfunction "4_4") (pintype "passive"))
      (node (ref "U$10") (pin "RST") (pinfunction "RST_RST") (pintype "bidirectional"))
      (node (ref "U$24") (pin "RST") (pinfunction "RST_RST") (pintype "bidirectional"))
    )
    (net (code "28") (name "/~{STEP-ENABLE-E}") (class "Default")
      (node (ref "U$46") (pin "4") (pinfunction "ENBL_4") (pintype "bidirectional"))
    )
    (net (code "29") (name "/~{STEP-ENABLE-XY}") (class "Default")
      (node (ref "IC2") (pin "35") (pinfunction "PCINT5/ADC5_PA5_35") (pintype "bidirectional"))
      (node (ref "R8") (pin "P$1") (pinfunction "1_P$1") (pintype "passive"))
      (node (ref "U$21") (pin "4") (pinfunction "ENBL_4") (pintype "bidirectional"))
      (node (ref "U$41") (pin "4") (pinfunction "ENBL_4") (pintype "bidirectional"))
    )
    (net (code "30") (name "5V") (class "Default")
      (node (ref "C13") (pin "2") (pinfunction "2_2") (pintype "passive"))
      (node (ref "C14") (pin "1") (pinfunction "1_1") (pintype "passive"))
      (node (ref "C6") (pin "1") (pinfunction "1_1") (pintype "passive"))
      (node (ref "IC1") (pin "OUT") (pinfunction "OUT_OUT") (pintype "output"))
      (node (ref "IC2") (pin "10") (pinfunction "VCC_10") (pintype "power_in"))
      (node (ref "IC2") (pin "30") (pinfunction "AVCC_30") (pintype "power_in"))
      (node (ref "IC2") (pin "32") (pinfunction "AREF_32") (pintype "passive"))
      (node (ref "JP1") (pin "2") (pinfunction "2_2") (pintype "passive"))
      (node (ref "JP10") (pin "2") (pinfunction "2_2") (pintype "passive"))
      (node (ref "JP12") (pin "2") (pinfunction "2_2") (pintype "passive"))
      (node (ref "JP13") (pin "2") (pinfunction "2_2") (pintype "passive"))
      (node (ref "JP14") (pin "2") (pinfunction "2_2") (pintype "passive"))
      (node (ref "JP15") (pin "2") (pinfunction "2_2") (pintype "passive"))
      (node (ref "JP16") (pin "2") (pinfunction "2_2") (pintype "passive"))
      (node (ref "JP17") (pin "2") (pinfunction "2_2") (pintype "passive"))
      (node (ref "JP18") (pin "2") (pinfunction "2_2") (pintype "passive"))
      (node (ref "JP19") (pin "2") (pinfunction "2_2") (pintype "passive"))
      (node (ref "JP20") (pin "2") (pinfunction "2_2") (pintype "passive"))
      (node (ref "JP21") (pin "2") (pinfunction "2_2") (pintype "passive"))
      (node (ref "JP27") (pin "2") (pinfunction "2_2") (pintype "passive"))
      (node (ref "JP28") (pin "2") (pinfunction "2_2") (pintype "passive"))
      (node (ref "JP29") (pin "2") (pinfunction "2_2") (pintype "passive"))
      (node (ref "JP3") (pin "2") (pinfunction "2_2") (pintype "passive"))
      (node (ref "JP30") (pin "2") (pinfunction "2_2") (pintype "passive"))
      (node (ref "JP32") (pin "2") (pinfunction "2_2") (pintype "passive"))
      (node (ref "JP33") (pin "2") (pinfunction "2_2") (pintype "passive"))
      (node (ref "JP34") (pin "2") (pinfunction "2_2") (pintype "passive"))
      (node (ref "JP35") (pin "2") (pinfunction "2_2") (pintype "passive"))
      (node (ref "JP36") (pin "2") (pinfunction "2_2") (pintype "passive"))
      (node (ref "JP37") (pin "2") (pinfunction "2_2") (pintype "passive"))
      (node (ref "JP38") (pin "1") (pinfunction "1_1") (pintype "passive"))
      (node (ref "JP5") (pin "2") (pinfunction "2_2") (pintype "passive"))
      (node (ref "JP8") (pin "2") (pinfunction "2_2") (pintype "passive"))
      (node (ref "JP9") (pin "2") (pinfunction "2_2") (pintype "passive"))
      (node (ref "R1") (pin "P$2") (pinfunction "2_P$2") (pintype "passive"))
      (node (ref "R10") (pin "P$2") (pinfunction "2_P$2") (pintype "passive"))
      (node (ref "R12") (pin "P$2") (pinfunction "2_P$2") (pintype "passive"))
      (node (ref "R8") (pin "P$2") (pinfunction "2_P$2") (pintype "passive"))
      (node (ref "R9") (pin "P$2") (pinfunction "2_P$2") (pintype "passive"))
      (node (ref "SV2") (pin "2") (pinfunction "2_2") (pintype "passive"))
      (node (ref "U$10") (pin "5V") (pinfunction "5V_5V") (pintype "bidirectional"))
      (node (ref "U$21") (pin "20") (pinfunction "VDD_20") (pintype "bidirectional"))
      (node (ref "U$21") (pin "5") (pinfunction "_RESET_5") (pintype "bidirectional"))
      (node (ref "U$24") (pin "5V") (pinfunction "5V_5V") (pintype "bidirectional"))
      (node (ref "U$41") (pin "20") (pinfunction "VDD_20") (pintype "bidirectional"))
      (node (ref "U$41") (pin "5") (pinfunction "_RESET_5") (pintype "bidirectional"))
      (node (ref "U$43") (pin "20") (pinfunction "VDD_20") (pintype "bidirectional"))
      (node (ref "U$43") (pin "5") (pinfunction "_RESET_5") (pintype "bidirectional"))
      (node (ref "U$46") (pin "20") (pinfunction "VDD_20") (pintype "bidirectional"))
      (node (ref "U$46") (pin "5") (pinfunction "_RESET_5") (pintype "bidirectional"))
    )
    (net (code "31") (name "12V") (class "Default")
      (node (ref "C12") (pin "1") (pinfunction "+_1") (pintype "passive"))
      (node (ref "JP23") (pin "1") (pinfunction "1_1") (pintype "passive"))
    )
    (net (code "32") (name "GND") (class "Default")
      (node (ref "C10") (pin "2") (pinfunction "-_2") (pintype "passive"))
      (node (ref "C11") (pin "2") (pinfunction "-_2") (pintype "passive"))
      (node (ref "C12") (pin "2") (pinfunction "-_2") (pintype "passive"))
      (node (ref "C13") (pin "1") (pinfunction "1_1") (pintype "passive"))
      (node (ref "C14") (pin "2") (pinfunction "2_2") (pintype "passive"))
      (node (ref "C15") (pin "1") (pinfunction "1_1") (pintype "passive"))
      (node (ref "C16") (pin "1") (pinfunction "1_1") (pintype "passive"))
      (node (ref "C17") (pin "2") (pinfunction "-_2") (pintype "passive"))
      (node (ref "C18") (pin "1") (pinfunction "1_1") (pintype "passive"))
      (node (ref "C19") (pin "1") (pinfunction "1_1") (pintype "passive"))
      (node (ref "C2") (pin "2") (pinfunction "-_2") (pintype "passive"))
      (node (ref "C20") (pin "2") (pinfunction "-_2") (pintype "passive"))
      (node (ref "C21") (pin "1") (pinfunction "1_1") (pintype "passive"))
      (node (ref "C22") (pin "1") (pinfunction "1_1") (pintype "passive"))
      (node (ref "C23") (pin "2") (pinfunction "-_2") (pintype "passive"))
      (node (ref "C3") (pin "-") (pinfunction "-_-") (pintype "passive"))
      (node (ref "C4") (pin "2") (pinfunction "2_2") (pintype "passive"))
      (node (ref "C5") (pin "2") (pinfunction "2_2") (pintype "passive"))
      (node (ref "C6") (pin "2") (pinfunction "2_2") (pintype "passive"))
      (node (ref "C7") (pin "1") (pinfunction "1_1") (pintype "passive"))
      (node (ref "C8") (pin "1") (pinfunction "1_1") (pintype "passive"))
      (node (ref "C9") (pin "2") (pinfunction "-_2") (pintype "passive"))
      (node (ref "D2") (pin "A") (pinfunction "A_A") (pintype "passive"))
      (node (ref "IC1") (pin "GND") (pinfunction "GND_GND") (pintype "input"))
      (node (ref "IC2") (pin "11") (pinfunction "GND_11") (pintype "power_in"))
      (node (ref "IC2") (pin "31") (pinfunction "GND_31") (pintype "power_in"))
      (node (ref "JP22") (pin "2") (pinfunction "2_2") (pintype "passive"))
      (node (ref "JP23") (pin "2") (pinfunction "2_2") (pintype "passive"))
      (node (ref "JP24") (pin "2") (pinfunction "2_2") (pintype "passive"))
      (node (ref "JP27") (pin "3") (pinfunction "3_3") (pintype "passive"))
      (node (ref "JP28") (pin "3") (pinfunction "3_3") (pintype "passive"))
      (node (ref "JP29") (pin "3") (pinfunction "3_3") (pintype "passive"))
      (node (ref "LED1") (pin "K") (pinfunction "C_K") (pintype "passive"))
      (node (ref "LED2") (pin "K") (pinfunction "C_K") (pintype "passive"))
      (node (ref "Q1") (pin "S") (pinfunction "S_S") (pintype "passive"))
      (node (ref "Q3") (pin "S") (pinfunction "S_S") (pintype "passive"))
      (node (ref "Q4") (pin "S") (pinfunction "S_S") (pintype "passive"))
      (node (ref "R13") (pin "2") (pinfunction "2_2") (pintype "passive"))
      (node (ref "R14") (pin "2") (pinfunction "2_2") (pintype "passive"))
      (node (ref "R15") (pin "2") (pinfunction "2_2") (pintype "passive"))
      (node (ref "R16") (pin "2") (pinfunction "2_2") (pintype "passive"))
      (node (ref "R17") (pin "2") (pinfunction "2_2") (pintype "passive"))
      (node (ref "R18") (pin "2") (pinfunction "2_2") (pintype "passive"))
      (node (ref "R19") (pin "2") (pinfunction "2_2") (pintype "passive"))
      (node (ref "R20") (pin "2") (pinfunction "2_2") (pintype "passive"))
      (node (ref "R21") (pin "2") (pinfunction "2_2") (pintype "passive"))
      (node (ref "R22") (pin "2") (pinfunction "2_2") (pintype "passive"))
      (node (ref "R23") (pin "2") (pinfunction "2_2") (pintype "passive"))
      (node (ref "R24") (pin "2") (pinfunction "2_2") (pintype "passive"))
      (node (ref "R25") (pin "2") (pinfunction "2_2") (pintype "passive"))
      (node (ref "R26") (pin "2") (pinfunction "2_2") (pintype "passive"))
      (node (ref "R27") (pin "2") (pinfunction "2_2") (pintype "passive"))
      (node (ref "R28") (pin "2") (pinfunction "2_2") (pintype "passive"))
      (node (ref "R4") (pin "2") (pinfunction "2_2") (pintype "passive"))
      (node (ref "R5") (pin "2") (pinfunction "2_2") (pintype "passive"))
      (node (ref "S1") (pin "1") (pinfunction "1_1") (pintype "passive"))
      (node (ref "S1") (pin "2") (pinfunction "2_2") (pintype "passive"))
      (node (ref "SV2") (pin "1") (pinfunction "1_1") (pintype "passive"))
      (node (ref "SV3") (pin "1") (pinfunction "1_1") (pintype "passive"))
      (node (ref "SV3") (pin "2") (pinfunction "2_2") (pintype "passive"))
      (node (ref "U$10") (pin "GND") (pinfunction "GND_GND") (pintype "bidirectional"))
      (node (ref "U$17") (pin "GND") (pinfunction "GND-SCREW_GND") (pintype "bidirectional"))
      (node (ref "U$21") (pin "10") (pinfunction "GND-B_10") (pintype "bidirectional"))
      (node (ref "U$21") (pin "15") (pinfunction "GND-A_15") (pintype "bidirectional"))
      (node (ref "U$21") (pin "6") (pinfunction "S-GND_6") (pintype "bidirectional"))
      (node (ref "U$24") (pin "GND") (pinfunction "GND_GND") (pintype "bidirectional"))
      (node (ref "U$24") (pin "GNDSCREW") (pinfunction "GND-SCREW_GNDSCREW") (pintype "bidirectional"))
      (node (ref "U$37") (pin "GND") (pinfunction "GND-SCREW_GND") (pintype "bidirectional"))
      (node (ref "U$38") (pin "GND") (pinfunction "GND-SCREW_GND") (pintype "bidirectional"))
      (node (ref "U$41") (pin "10") (pinfunction "GND-B_10") (pintype "bidirectional"))
      (node (ref "U$41") (pin "15") (pinfunction "GND-A_15") (pintype "bidirectional"))
      (node (ref "U$41") (pin "6") (pinfunction "S-GND_6") (pintype "bidirectional"))
      (node (ref "U$43") (pin "10") (pinfunction "GND-B_10") (pintype "bidirectional"))
      (node (ref "U$43") (pin "15") (pinfunction "GND-A_15") (pintype "bidirectional"))
      (node (ref "U$43") (pin "6") (pinfunction "S-GND_6") (pintype "bidirectional"))
      (node (ref "U$46") (pin "10") (pinfunction "GND-B_10") (pintype "bidirectional"))
      (node (ref "U$46") (pin "15") (pinfunction "GND-A_15") (pintype "bidirectional"))
      (node (ref "U$46") (pin "6") (pinfunction "S-GND_6") (pintype "bidirectional"))
      (node (ref "X3") (pin "1") (pinfunction "KL_1") (pintype "passive"))
      (node (ref "X5") (pin "1") (pinfunction "KL_1") (pintype "passive"))
      (node (ref "Y1") (pin "2") (pinfunction "2_2") (pintype "passive"))
    )
    (net (code "33") (name "Net-(C1-Pad1)") (class "Default")
      (node (ref "C1") (pin "1") (pinfunction "1_1") (pintype "passive"))
      (node (ref "SV3") (pin "6") (pinfunction "6_6") (pintype "passive"))
    )
    (net (code "34") (name "Net-(C5-Pad1)") (class "Default")
      (node (ref "C5") (pin "1") (pinfunction "1_1") (pintype "passive"))
      (node (ref "D3") (pin "C") (pinfunction "C_C") (pintype "passive"))
      (node (ref "IC1") (pin "IN") (pinfunction "IN_IN") (pintype "input"))
    )
    (net (code "35") (name "Net-(IC2-PCINT16{slash}SCL_PC0)") (class "Default")
      (node (ref "IC2") (pin "22") (pinfunction "PCINT16/SCL_PC0_22") (pintype "bidirectional"))
      (node (ref "SV2") (pin "4") (pinfunction "4_4") (pintype "passive"))
    )
    (net (code "36") (name "Net-(IC2-PCINT17{slash}SDA_PC1)") (class "Default")
      (node (ref "IC2") (pin "23") (pinfunction "PCINT17/SDA_PC1_23") (pintype "bidirectional"))
      (node (ref "SV2") (pin "3") (pinfunction "3_3") (pintype "passive"))
    )
    (net (code "37") (name "Net-(IC2-PCINT26{slash}RDX1{slash}INT0_PD2)") (class "Default")
      (node (ref "IC2") (pin "16") (pinfunction "PCINT26/RDX1/INT0_PD2_16") (pintype "bidirectional"))
      (node (ref "SV1") (pin "5") (pinfunction "5_5") (pintype "passive"))
    )
    (net (code "38") (name "Net-(IC2-PCINT27{slash}TXD1{slash}INT1_PD3)") (class "Default")
      (node (ref "IC2") (pin "17") (pinfunction "PCINT27/TXD1/INT1_PD3_17") (pintype "bidirectional"))
      (node (ref "SV1") (pin "4") (pinfunction "4_4") (pintype "passive"))
    )
    (net (code "39") (name "Net-(IC2-PCINT28{slash}OC1B_PD4)") (class "Default")
      (node (ref "IC2") (pin "18") (pinfunction "PCINT28/OC1B_PD4_18") (pintype "bidirectional"))
      (node (ref "SV1") (pin "3") (pinfunction "3_3") (pintype "passive"))
    )
    (net (code "40") (name "Net-(IC2-PCINT29{slash}OC1A_PD5)") (class "Default")
      (node (ref "IC2") (pin "19") (pinfunction "PCINT29/OC1A_PD5_19") (pintype "bidirectional"))
      (node (ref "SV1") (pin "2") (pinfunction "2_2") (pintype "passive"))
    )
    (net (code "41") (name "Net-(IC2-PCINT30{slash}OC2B{slash}ICP_PD6)") (class "Default")
      (node (ref "IC2") (pin "20") (pinfunction "PCINT30/OC2B/ICP_PD6_20") (pintype "bidirectional"))
      (node (ref "SV1") (pin "1") (pinfunction "1_1") (pintype "passive"))
    )
    (net (code "42") (name "Net-(IC2-XTAL1)") (class "Default")
      (node (ref "IC2") (pin "13") (pinfunction "XTAL1_13") (pintype "input"))
      (node (ref "Y1") (pin "3") (pinfunction "3_3") (pintype "passive"))
    )
    (net (code "43") (name "Net-(IC2-XTAL2)") (class "Default")
      (node (ref "IC2") (pin "12") (pinfunction "XTAL2_12") (pintype "output"))
      (node (ref "Y1") (pin "1") (pinfunction "1_1") (pintype "passive"))
    )
    (net (code "44") (name "Net-(JP38-Pad2)") (class "Default")
      (node (ref "JP38") (pin "2") (pinfunction "2_2") (pintype "passive"))
      (node (ref "SV3") (pin "3") (pinfunction "3_3") (pintype "passive"))
    )
    (net (code "45") (name "Net-(K2A-2)") (class "Default")
      (node (ref "K2") (pin "A2") (pinfunction "2_A2") (pintype "passive"))
      (node (ref "R6") (pin "2") (pinfunction "2_2") (pintype "passive"))
    )
    (net (code "46") (name "Net-(K2B-S)") (class "Default")
      (node (ref "F2") (pin "1") (pinfunction "1_1") (pintype "passive"))
      (node (ref "K2") (pin "14") (pinfunction "S_14") (pintype "passive"))
    )
    (net (code "47") (name "Net-(LED2-PadA)") (class "Default")
      (node (ref "LED2") (pin "A") (pinfunction "A_A") (pintype "passive"))
      (node (ref "R31") (pin "1") (pinfunction "1_1") (pintype "passive"))
    )
    (net (code "48") (name "Net-(LED3-C)") (class "Default")
      (node (ref "LED3") (pin "K") (pinfunction "C_K") (pintype "passive"))
      (node (ref "Q4") (pin "D") (pinfunction "D_D") (pintype "passive"))
      (node (ref "X1") (pin "2") (pinfunction "KL_2") (pintype "passive"))
    )
    (net (code "49") (name "Net-(LED3-PadA)") (class "Default")
      (node (ref "LED3") (pin "A") (pinfunction "A_A") (pintype "passive"))
      (node (ref "R7") (pin "1") (pinfunction "1_1") (pintype "passive"))
    )
    (net (code "50") (name "Net-(LED5-C)") (class "Default")
      (node (ref "LED5") (pin "K") (pinfunction "C_K") (pintype "passive"))
      (node (ref "Q3") (pin "D") (pinfunction "D_D") (pintype "passive"))
      (node (ref "X2") (pin "2") (pinfunction "KL_2") (pintype "passive"))
    )
    (net (code "51") (name "Net-(LED5-PadA)") (class "Default")
      (node (ref "LED5") (pin "A") (pinfunction "A_A") (pintype "passive"))
      (node (ref "R29") (pin "1") (pinfunction "1_1") (pintype "passive"))
    )
    (net (code "52") (name "Net-(Q1-PadD)") (class "Default")
      (node (ref "Q1") (pin "D") (pinfunction "D_D") (pintype "passive"))
      (node (ref "R6") (pin "1") (pinfunction "1_1") (pintype "passive"))
    )
    (net (code "53") (name "Net-(Q1-PadG)") (class "Default")
      (node (ref "Q1") (pin "G") (pinfunction "G_G") (pintype "passive"))
      (node (ref "R30") (pin "2") (pinfunction "2_2") (pintype "passive"))
    )
    (net (code "54") (name "Net-(Q3-PadG)") (class "Default")
      (node (ref "Q3") (pin "G") (pinfunction "G_G") (pintype "passive"))
      (node (ref "R3") (pin "2") (pinfunction "2_2") (pintype "passive"))
    )
    (net (code "55") (name "Net-(Q4-PadG)") (class "Default")
      (node (ref "Q4") (pin "G") (pinfunction "G_G") (pintype "passive"))
      (node (ref "R2") (pin "2") (pinfunction "2_2") (pintype "passive"))
    )
    (net (code "56") (name "Net-(R1-1)") (class "Default")
      (node (ref "LED1") (pin "A") (pinfunction "A_A") (pintype "passive"))
      (node (ref "R1") (pin "P$1") (pinfunction "1_P$1") (pintype "passive"))
    )
    (net (code "57") (name "Net-(U$21-DCY-1)") (class "Default")
      (node (ref "JP19") (pin "1") (pinfunction "1_1") (pintype "passive"))
      (node (ref "U$21") (pin "25") (pinfunction "DCY-1_25") (pintype "bidirectional"))
    )
    (net (code "58") (name "Net-(U$21-DCY-2)") (class "Default")
      (node (ref "JP20") (pin "1") (pinfunction "1_1") (pintype "passive"))
      (node (ref "U$21") (pin "24") (pinfunction "DCY-2_24") (pintype "bidirectional"))
    )
    (net (code "59") (name "Net-(U$21-M1)") (class "Default")
      (node (ref "JP17") (pin "1") (pinfunction "1_1") (pintype "passive"))
      (node (ref "U$21") (pin "23") (pinfunction "M1_23") (pintype "bidirectional"))
    )
    (net (code "60") (name "Net-(U$21-M2)") (class "Default")
      (node (ref "JP18") (pin "1") (pinfunction "1_1") (pintype "passive"))
      (node (ref "U$21") (pin "22") (pinfunction "M2_22") (pintype "bidirectional"))
    )
    (net (code "61") (name "Net-(U$21-OSC)") (class "Default")
      (node (ref "C16") (pin "2") (pinfunction "2_2") (pintype "passive"))
      (node (ref "U$21") (pin "7") (pinfunction "OSC_7") (pintype "bidirectional"))
    )
    (net (code "62") (name "Net-(U$21-OUT-AM)") (class "Default")
      (node (ref "JP25") (pin "2") (pinfunction "2_2") (pintype "passive"))
      (node (ref "U$21") (pin "13") (pinfunction "OUT-AM_13") (pintype "output"))
    )
    (net (code "63") (name "Net-(U$21-OUT-AP)") (class "Default")
      (node (ref "JP25") (pin "1") (pinfunction "1_1") (pintype "passive"))
      (node (ref "U$21") (pin "16") (pinfunction "OUT-AP_16") (pintype "output"))
    )
    (net (code "64") (name "Net-(U$21-OUT-BM)") (class "Default")
      (node (ref "JP25") (pin "4") (pinfunction "4_4") (pintype "passive"))
      (node (ref "U$21") (pin "9") (pinfunction "OUT-BM_9") (pintype "output"))
    )
    (net (code "65") (name "Net-(U$21-OUT-BP)") (class "Default")
      (node (ref "JP25") (pin "3") (pinfunction "3_3") (pintype "passive"))
      (node (ref "U$21") (pin "12") (pinfunction "OUT-BP_12") (pintype "output"))
    )
    (net (code "66") (name "Net-(U$21-SENS-A)") (class "Default")
      (node (ref "R19") (pin "1") (pinfunction "1_1") (pintype "passive"))
      (node (ref "R20") (pin "1") (pinfunction "1_1") (pintype "passive"))
      (node (ref "U$21") (pin "14") (pinfunction "SENS-A_14") (pintype "bidirectional"))
    )
    (net (code "67") (name "Net-(U$21-SENS-B)") (class "Default")
      (node (ref "R17") (pin "1") (pinfunction "1_1") (pintype "passive"))
      (node (ref "R18") (pin "1") (pinfunction "1_1") (pintype "passive"))
      (node (ref "U$21") (pin "11") (pinfunction "SENS-B_11") (pintype "bidirectional"))
    )
    (net (code "68") (name "Net-(U$21-TQ1)") (class "Default")
      (node (ref "JP21") (pin "1") (pinfunction "1_1") (pintype "passive"))
      (node (ref "U$21") (pin "2") (pinfunction "TQ1_2") (pintype "bidirectional"))
    )
    (net (code "69") (name "Net-(U$21-TQ2)") (class "Default")
      (node (ref "JP30") (pin "1") (pinfunction "1_1") (pintype "passive"))
      (node (ref "U$21") (pin "1") (pinfunction "TQ2_1") (pintype "bidirectional"))
    )
    (net (code "70") (name "Net-(U$41-DCY-1)") (class "Default")
      (node (ref "JP13") (pin "1") (pinfunction "1_1") (pintype "passive"))
      (node (ref "U$41") (pin "25") (pinfunction "DCY-1_25") (pintype "bidirectional"))
    )
    (net (code "71") (name "Net-(U$41-DCY-2)") (class "Default")
      (node (ref "JP14") (pin "1") (pinfunction "1_1") (pintype "passive"))
      (node (ref "U$41") (pin "24") (pinfunction "DCY-2_24") (pintype "bidirectional"))
    )
    (net (code "72") (name "Net-(U$41-M1)") (class "Default")
      (node (ref "JP11") (pin "1") (pinfunction "1_1") (pintype "passive"))
      (node (ref "U$41") (pin "23") (pinfunction "M1_23") (pintype "bidirectional"))
    )
    (net (code "73") (name "Net-(U$41-M2)") (class "Default")
      (node (ref "JP12") (pin "1") (pinfunction "1_1") (pintype "passive"))
      (node (ref "U$41") (pin "22") (pinfunction "M2_22") (pintype "bidirectional"))
    )
    (net (code "74") (name "Net-(U$41-OSC)") (class "Default")
      (node (ref "C8") (pin "2") (pinfunction "2_2") (pintype "passive"))
      (node (ref "U$41") (pin "7") (pinfunction "OSC_7") (pintype "bidirectional"))
    )
    (net (code "75") (name "Net-(U$41-OUT-AM)") (class "Default")
      (node (ref "JP7") (pin "2") (pinfunction "2_2") (pintype "passive"))
      (node (ref "U$41") (pin "13") (pinfunction "OUT-AM_13") (pintype "output"))
    )
    (net (code "76") (name "Net-(U$41-OUT-AP)") (class "Default")
      (node (ref "JP7") (pin "1") (pinfunction "1_1") (pintype "passive"))
      (node (ref "U$41") (pin "16") (pinfunction "OUT-AP_16") (pintype "output"))
    )
    (net (code "77") (name "Net-(U$41-OUT-BM)") (class "Default")
      (node (ref "JP7") (pin "4") (pinfunction "4_4") (pintype "passive"))
      (node (ref "U$41") (pin "9") (pinfunction "OUT-BM_9") (pintype "output"))
    )
    (net (code "78") (name "Net-(U$41-OUT-BP)") (class "Default")
      (node (ref "JP7") (pin "3") (pinfunction "3_3") (pintype "passive"))
      (node (ref "U$41") (pin "12") (pinfunction "OUT-BP_12") (pintype "output"))
    )
    (net (code "79") (name "Net-(U$41-SENS-A)") (class "Default")
      (node (ref "R15") (pin "1") (pinfunction "1_1") (pintype "passive"))
      (node (ref "R16") (pin "1") (pinfunction "1_1") (pintype "passive"))
      (node (ref "U$41") (pin "14") (pinfunction "SENS-A_14") (pintype "bidirectional"))
    )
    (net (code "80") (name "Net-(U$41-SENS-B)") (class "Default")
      (node (ref "R13") (pin "1") (pinfunction "1_1") (pintype "passive"))
      (node (ref "R14") (pin "1") (pinfunction "1_1") (pintype "passive"))
      (node (ref "U$41") (pin "11") (pinfunction "SENS-B_11") (pintype "bidirectional"))
    )
    (net (code "81") (name "Net-(U$41-TQ1)") (class "Default")
      (node (ref "JP15") (pin "1") (pinfunction "1_1") (pintype "passive"))
      (node (ref "U$41") (pin "2") (pinfunction "TQ1_2") (pintype "bidirectional"))
    )
    (net (code "82") (name "Net-(U$41-TQ2)") (class "Default")
      (node (ref "JP16") (pin "1") (pinfunction "1_1") (pintype "passive"))
      (node (ref "U$41") (pin "1") (pinfunction "TQ2_1") (pintype "bidirectional"))
    )
    (net (code "83") (name "Net-(U$43-DCY-1)") (class "Default")
      (node (ref "JP5") (pin "1") (pinfunction "1_1") (pintype "passive"))
      (node (ref "U$43") (pin "25") (pinfunction "DCY-1_25") (pintype "bidirectional"))
    )
    (net (code "84") (name "Net-(U$43-DCY-2)") (class "Default")
      (node (ref "JP8") (pin "1") (pinfunction "1_1") (pintype "passive"))
      (node (ref "U$43") (pin "24") (pinfunction "DCY-2_24") (pintype "bidirectional"))
    )
    (net (code "85") (name "Net-(U$43-M1)") (class "Default")
      (node (ref "JP1") (pin "1") (pinfunction "1_1") (pintype "passive"))
      (node (ref "U$43") (pin "23") (pinfunction "M1_23") (pintype "bidirectional"))
    )
    (net (code "86") (name "Net-(U$43-M2)") (class "Default")
      (node (ref "JP3") (pin "1") (pinfunction "1_1") (pintype "passive"))
      (node (ref "U$43") (pin "22") (pinfunction "M2_22") (pintype "bidirectional"))
    )
    (net (code "87") (name "Net-(U$43-OSC)") (class "Default")
      (node (ref "C19") (pin "2") (pinfunction "2_2") (pintype "passive"))
      (node (ref "U$43") (pin "7") (pinfunction "OSC_7") (pintype "bidirectional"))
    )
    (net (code "88") (name "Net-(U$43-OUT-AM)") (class "Default")
      (node (ref "JP26") (pin "2") (pinfunction "2_2") (pintype "passive"))
      (node (ref "U$43") (pin "13") (pinfunction "OUT-AM_13") (pintype "output"))
    )
    (net (code "89") (name "Net-(U$43-OUT-AP)") (class "Default")
      (node (ref "JP26") (pin "1") (pinfunction "1_1") (pintype "passive"))
      (node (ref "U$43") (pin "16") (pinfunction "OUT-AP_16") (pintype "output"))
    )
    (net (code "90") (name "Net-(U$43-OUT-BM)") (class "Default")
      (node (ref "JP26") (pin "4") (pinfunction "4_4") (pintype "passive"))
      (node (ref "U$43") (pin "9") (pinfunction "OUT-BM_9") (pintype "output"))
    )
    (net (code "91") (name "Net-(U$43-OUT-BP)") (class "Default")
      (node (ref "JP26") (pin "3") (pinfunction "3_3") (pintype "passive"))
      (node (ref "U$43") (pin "12") (pinfunction "OUT-BP_12") (pintype "output"))
    )
    (net (code "92") (name "Net-(U$43-SENS-A)") (class "Default")
      (node (ref "R23") (pin "1") (pinfunction "1_1") (pintype "passive"))
      (node (ref "R24") (pin "1") (pinfunction "1_1") (pintype "passive"))
      (node (ref "U$43") (pin "14") (pinfunction "SENS-A_14") (pintype "bidirectional"))
    )
    (net (code "93") (name "Net-(U$43-SENS-B)") (class "Default")
      (node (ref "R21") (pin "1") (pinfunction "1_1") (pintype "passive"))
      (node (ref "R22") (pin "1") (pinfunction "1_1") (pintype "passive"))
      (node (ref "U$43") (pin "11") (pinfunction "SENS-B_11") (pintype "bidirectional"))
    )
    (net (code "94") (name "Net-(U$43-TQ1)") (class "Default")
      (node (ref "JP9") (pin "1") (pinfunction "1_1") (pintype "passive"))
      (node (ref "U$43") (pin "2") (pinfunction "TQ1_2") (pintype "bidirectional"))
    )
    (net (code "95") (name "Net-(U$43-TQ2)") (class "Default")
      (node (ref "JP10") (pin "1") (pinfunction "1_1") (pintype "passive"))
      (node (ref "U$43") (pin "1") (pinfunction "TQ2_1") (pintype "bidirectional"))
    )
    (net (code "96") (name "Net-(U$46-DCY-1)") (class "Default")
      (node (ref "JP34") (pin "1") (pinfunction "1_1") (pintype "passive"))
      (node (ref "U$46") (pin "25") (pinfunction "DCY-1_25") (pintype "bidirectional"))
    )
    (net (code "97") (name "Net-(U$46-DCY-2)") (class "Default")
      (node (ref "JP35") (pin "1") (pinfunction "1_1") (pintype "passive"))
      (node (ref "U$46") (pin "24") (pinfunction "DCY-2_24") (pintype "bidirectional"))
    )
    (net (code "98") (name "Net-(U$46-M1)") (class "Default")
      (node (ref "JP32") (pin "1") (pinfunction "1_1") (pintype "passive"))
      (node (ref "U$46") (pin "23") (pinfunction "M1_23") (pintype "bidirectional"))
    )
    (net (code "99") (name "Net-(U$46-M2)") (class "Default")
      (node (ref "JP33") (pin "1") (pinfunction "1_1") (pintype "passive"))
      (node (ref "U$46") (pin "22") (pinfunction "M2_22") (pintype "bidirectional"))
    )
    (net (code "100") (name "Net-(U$46-OSC)") (class "Default")
      (node (ref "C22") (pin "2") (pinfunction "2_2") (pintype "passive"))
      (node (ref "U$46") (pin "7") (pinfunction "OSC_7") (pintype "bidirectional"))
    )
    (net (code "101") (name "Net-(U$46-OUT-AM)") (class "Default")
      (node (ref "JP31") (pin "2") (pinfunction "2_2") (pintype "passive"))
      (node (ref "U$46") (pin "13") (pinfunction "OUT-AM_13") (pintype "output"))
    )
    (net (code "102") (name "Net-(U$46-OUT-AP)") (class "Default")
      (node (ref "JP31") (pin "1") (pinfunction "1_1") (pintype "passive"))
      (node (ref "U$46") (pin "16") (pinfunction "OUT-AP_16") (pintype "output"))
    )
    (net (code "103") (name "Net-(U$46-OUT-BM)") (class "Default")
      (node (ref "JP31") (pin "4") (pinfunction "4_4") (pintype "passive"))
      (node (ref "U$46") (pin "9") (pinfunction "OUT-BM_9") (pintype "output"))
    )
    (net (code "104") (name "Net-(U$46-OUT-BP)") (class "Default")
      (node (ref "JP31") (pin "3") (pinfunction "3_3") (pintype "passive"))
      (node (ref "U$46") (pin "12") (pinfunction "OUT-BP_12") (pintype "output"))
    )
    (net (code "105") (name "Net-(U$46-SENS-A)") (class "Default")
      (node (ref "R27") (pin "1") (pinfunction "1_1") (pintype "passive"))
      (node (ref "R28") (pin "1") (pinfunction "1_1") (pintype "passive"))
      (node (ref "U$46") (pin "14") (pinfunction "SENS-A_14") (pintype "bidirectional"))
    )
    (net (code "106") (name "Net-(U$46-SENS-B)") (class "Default")
      (node (ref "R25") (pin "1") (pinfunction "1_1") (pintype "passive"))
      (node (ref "R26") (pin "1") (pinfunction "1_1") (pintype "passive"))
      (node (ref "U$46") (pin "11") (pinfunction "SENS-B_11") (pintype "bidirectional"))
    )
    (net (code "107") (name "Net-(U$46-TQ1)") (class "Default")
      (node (ref "JP36") (pin "1") (pinfunction "1_1") (pintype "passive"))
      (node (ref "U$46") (pin "2") (pinfunction "TQ1_2") (pintype "bidirectional"))
    )
    (net (code "108") (name "Net-(U$46-TQ2)") (class "Default")
      (node (ref "JP37") (pin "1") (pinfunction "1_1") (pintype "passive"))
      (node (ref "U$46") (pin "1") (pinfunction "TQ2_1") (pintype "bidirectional"))
    )
    (net (code "109") (name "Net-(X5B-KL)") (class "Default")
      (node (ref "F1") (pin "2") (pinfunction "2_2") (pintype "passive"))
      (node (ref "X5") (pin "2") (pinfunction "KL_2") (pintype "passive"))
    )
    (net (code "110") (name "unconnected-(IC2-PCINT18{slash}TCK_PC2-Pad24)") (class "Default")
      (node (ref "IC2") (pin "24") (pinfunction "PCINT18/TCK_PC2_24") (pintype "bidirectional"))
    )
    (net (code "111") (name "unconnected-(IC2-PCINT20{slash}TDO_PC4-Pad26)") (class "Default")
      (node (ref "IC2") (pin "26") (pinfunction "PCINT20/TDO_PC4_26") (pintype "bidirectional"))
    )
    (net (code "112") (name "unconnected-(IC2-PCINT31{slash}OC2A_PD7-Pad21)") (class "Default")
      (node (ref "IC2") (pin "21") (pinfunction "PCINT31/OC2A_PD7_21") (pintype "bidirectional"))
    )
    (net (code "113") (name "unconnected-(JP11-Pad2)") (class "Default")
      (node (ref "JP11") (pin "2") (pinfunction "2_2") (pintype "passive"))
    )
    (net (code "114") (name "unconnected-(K2B-O-Pad12)") (class "Default")
      (node (ref "K2") (pin "12") (pinfunction "O_12") (pintype "passive"))
    )
    (net (code "115") (name "unconnected-(SV2-Pad5)") (class "Default")
      (node (ref "SV2") (pin "5") (pinfunction "5_5") (pintype "passive"))
    )
    (net (code "116") (name "unconnected-(U$21-MO-Pad17)") (class "Default")
      (node (ref "U$21") (pin "17") (pinfunction "MO_17") (pintype "bidirectional"))
    )
    (net (code "117") (name "unconnected-(U$21-PROTECT-Pad19)") (class "Default")
      (node (ref "U$21") (pin "19") (pinfunction "PROTECT_19") (pintype "bidirectional"))
    )
    (net (code "118") (name "unconnected-(U$41-MO-Pad17)") (class "Default")
      (node (ref "U$41") (pin "17") (pinfunction "MO_17") (pintype "bidirectional"))
    )
    (net (code "119") (name "unconnected-(U$41-PROTECT-Pad19)") (class "Default")
      (node (ref "U$41") (pin "19") (pinfunction "PROTECT_19") (pintype "bidirectional"))
    )
    (net (code "120") (name "unconnected-(U$43-MO-Pad17)") (class "Default")
      (node (ref "U$43") (pin "17") (pinfunction "MO_17") (pintype "bidirectional"))
    )
    (net (code "121") (name "unconnected-(U$43-PROTECT-Pad19)") (class "Default")
      (node (ref "U$43") (pin "19") (pinfunction "PROTECT_19") (pintype "bidirectional"))
    )
    (net (code "122") (name "unconnected-(U$46-MO-Pad17)") (class "Default")
      (node (ref "U$46") (pin "17") (pinfunction "MO_17") (pintype "bidirectional"))
    )
    (net (code "123") (name "unconnected-(U$46-PROTECT-Pad19)") (class "Default")
      (node (ref "U$46") (pin "19") (pinfunction "PROTECT_19") (pintype "bidirectional"))
    )
  )
)
